# Apollo_v1.net
KiCad netlist of a schematic drawn in EAGLE
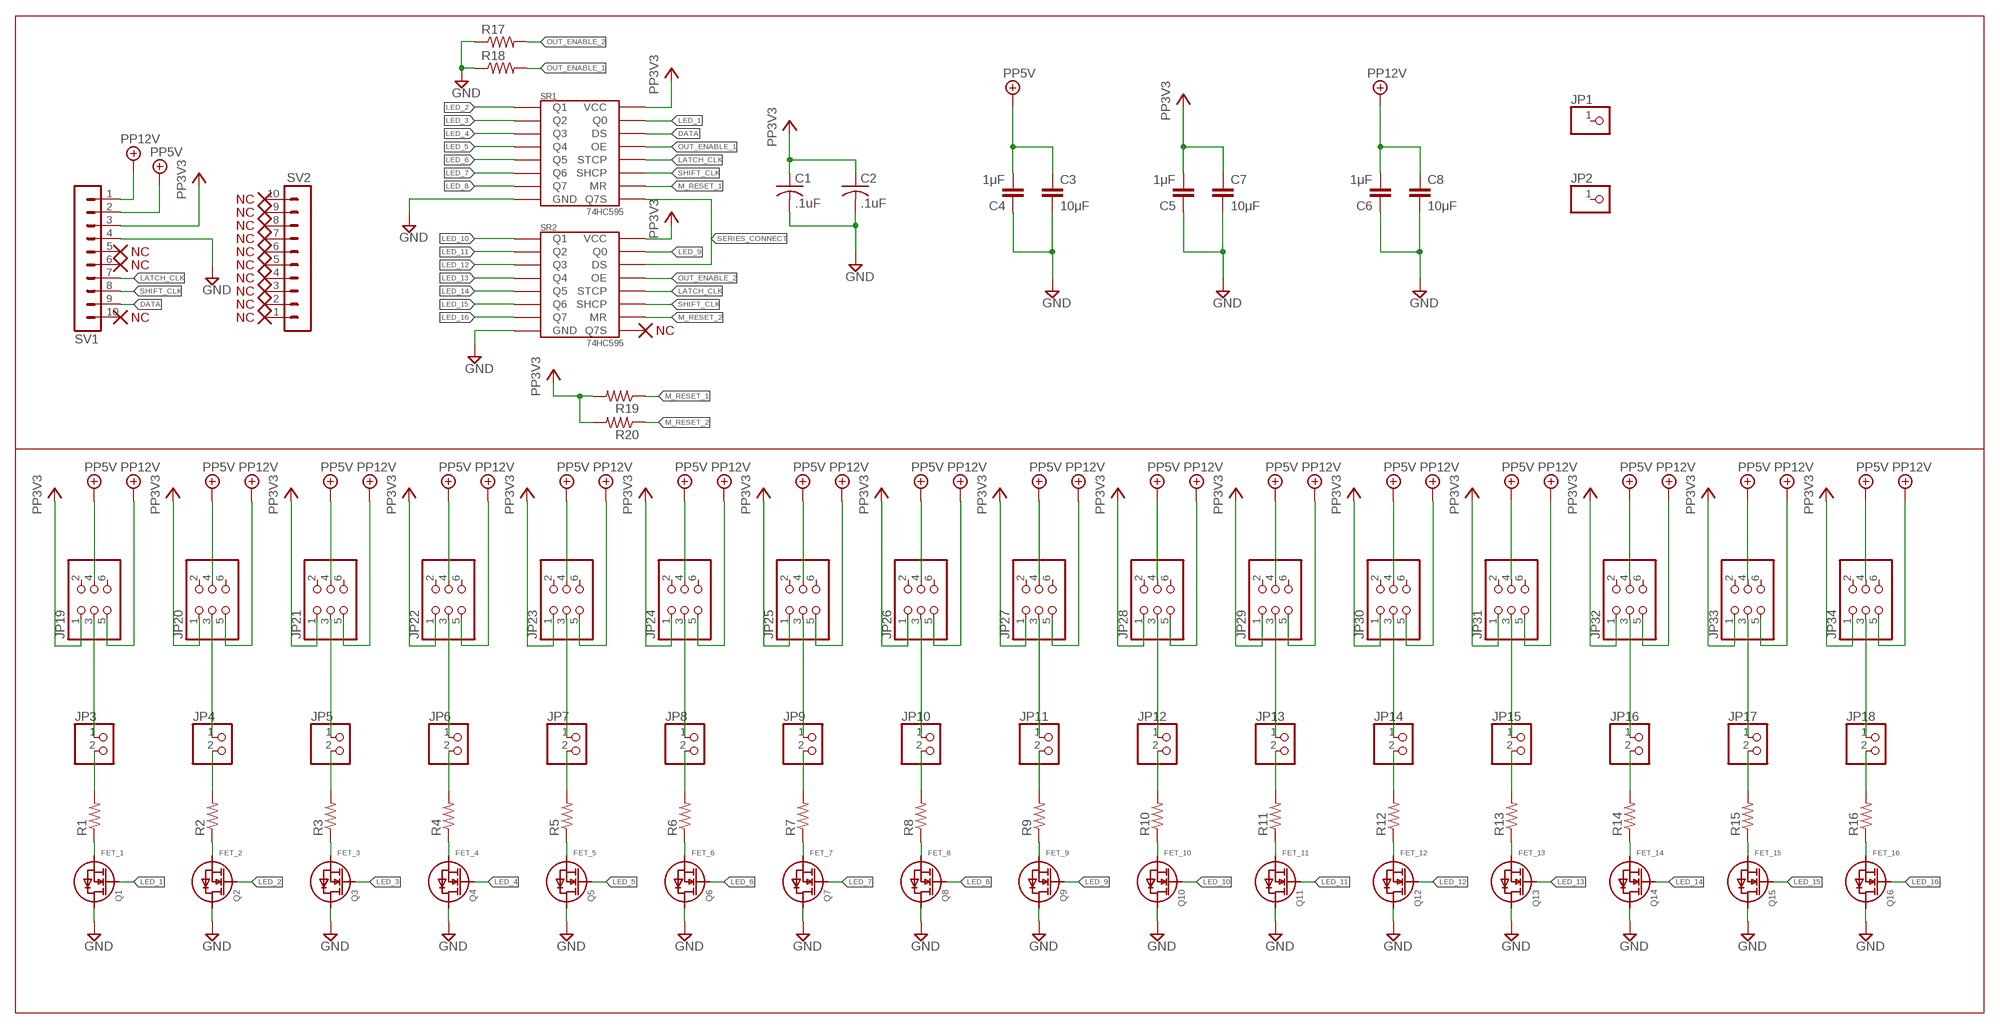
[diagram p0: schematic, sheet 1]

(export (version "E")
  (design (tool "Eeschema 10.0.6"))
  (components
    (comp (ref "C1")
      (value ".1uF")
      (footprint "eagle-import:C0603")
      (libsource (lib "eagle-import") (part "C-USC0603"))
    )
    (comp (ref "C2")
      (value ".1uF")
      (footprint "eagle-import:C0603")
      (libsource (lib "eagle-import") (part "C-USC0603"))
    )
    (comp (ref "C3")
      (value "10μF")
      (footprint "eagle-import:C1206")
      (libsource (lib "eagle-import") (part "C-EUC1206"))
    )
    (comp (ref "C4")
      (value "1μF")
      (footprint "eagle-import:C0603")
      (libsource (lib "eagle-import") (part "C-EUC0603"))
    )
    (comp (ref "C5")
      (value "1μF")
      (footprint "eagle-import:C0603")
      (libsource (lib "eagle-import") (part "C-EUC0603"))
    )
    (comp (ref "C6")
      (value "1μF")
      (footprint "eagle-import:C0603")
      (libsource (lib "eagle-import") (part "C-EUC0603"))
    )
    (comp (ref "C7")
      (value "10μF")
      (footprint "eagle-import:C1206")
      (libsource (lib "eagle-import") (part "C-EUC1206"))
    )
    (comp (ref "C8")
      (value "10μF")
      (footprint "eagle-import:C1206")
      (libsource (lib "eagle-import") (part "C-EUC1206"))
    )
    (comp (ref "JP1")
      (value "PINHD-1X1")
      (footprint "eagle-import:1X01")
      (libsource (lib "eagle-import") (part "PINHD-1X1"))
    )
    (comp (ref "JP2")
      (value "PINHD-1X1")
      (footprint "eagle-import:1X01")
      (libsource (lib "eagle-import") (part "PINHD-1X1"))
    )
    (comp (ref "JP3")
      (value "PINHD-1X2")
      (footprint "eagle-import:1X02")
      (libsource (lib "eagle-import") (part "PINHD-1X2"))
    )
    (comp (ref "JP4")
      (value "PINHD-1X2")
      (footprint "eagle-import:1X02")
      (libsource (lib "eagle-import") (part "PINHD-1X2"))
    )
    (comp (ref "JP5")
      (value "PINHD-1X2")
      (footprint "eagle-import:1X02")
      (libsource (lib "eagle-import") (part "PINHD-1X2"))
    )
    (comp (ref "JP6")
      (value "PINHD-1X2")
      (footprint "eagle-import:1X02")
      (libsource (lib "eagle-import") (part "PINHD-1X2"))
    )
    (comp (ref "JP7")
      (value "PINHD-1X2")
      (footprint "eagle-import:1X02")
      (libsource (lib "eagle-import") (part "PINHD-1X2"))
    )
    (comp (ref "JP8")
      (value "PINHD-1X2")
      (footprint "eagle-import:1X02")
      (libsource (lib "eagle-import") (part "PINHD-1X2"))
    )
    (comp (ref "JP9")
      (value "PINHD-1X2")
      (footprint "eagle-import:1X02")
      (libsource (lib "eagle-import") (part "PINHD-1X2"))
    )
    (comp (ref "JP10")
      (value "PINHD-1X2")
      (footprint "eagle-import:1X02")
      (libsource (lib "eagle-import") (part "PINHD-1X2"))
    )
    (comp (ref "JP11")
      (value "PINHD-1X2")
      (footprint "eagle-import:1X02")
      (libsource (lib "eagle-import") (part "PINHD-1X2"))
    )
    (comp (ref "JP12")
      (value "PINHD-1X2")
      (footprint "eagle-import:1X02")
      (libsource (lib "eagle-import") (part "PINHD-1X2"))
    )
    (comp (ref "JP13")
      (value "PINHD-1X2")
      (footprint "eagle-import:1X02")
      (libsource (lib "eagle-import") (part "PINHD-1X2"))
    )
    (comp (ref "JP14")
      (value "PINHD-1X2")
      (footprint "eagle-import:1X02")
      (libsource (lib "eagle-import") (part "PINHD-1X2"))
    )
    (comp (ref "JP15")
      (value "PINHD-1X2")
      (footprint "eagle-import:1X02")
      (libsource (lib "eagle-import") (part "PINHD-1X2"))
    )
    (comp (ref "JP16")
      (value "PINHD-1X2")
      (footprint "eagle-import:1X02")
      (libsource (lib "eagle-import") (part "PINHD-1X2"))
    )
    (comp (ref "JP17")
      (value "PINHD-1X2")
      (footprint "eagle-import:1X02")
      (libsource (lib "eagle-import") (part "PINHD-1X2"))
    )
    (comp (ref "JP18")
      (value "PINHD-1X2")
      (footprint "eagle-import:1X02")
      (libsource (lib "eagle-import") (part "PINHD-1X2"))
    )
    (comp (ref "JP19")
      (value "PINHD-2X3")
      (footprint "eagle-import:2X03")
      (libsource (lib "eagle-import") (part "PINHD-2X3"))
    )
    (comp (ref "JP20")
      (value "PINHD-2X3")
      (footprint "eagle-import:2X03")
      (libsource (lib "eagle-import") (part "PINHD-2X3"))
    )
    (comp (ref "JP21")
      (value "PINHD-2X3")
      (footprint "eagle-import:2X03")
      (libsource (lib "eagle-import") (part "PINHD-2X3"))
    )
    (comp (ref "JP22")
      (value "PINHD-2X3")
      (footprint "eagle-import:2X03")
      (libsource (lib "eagle-import") (part "PINHD-2X3"))
    )
    (comp (ref "JP23")
      (value "PINHD-2X3")
      (footprint "eagle-import:2X03")
      (libsource (lib "eagle-import") (part "PINHD-2X3"))
    )
    (comp (ref "JP24")
      (value "PINHD-2X3")
      (footprint "eagle-import:2X03")
      (libsource (lib "eagle-import") (part "PINHD-2X3"))
    )
    (comp (ref "JP25")
      (value "PINHD-2X3")
      (footprint "eagle-import:2X03")
      (libsource (lib "eagle-import") (part "PINHD-2X3"))
    )
    (comp (ref "JP26")
      (value "PINHD-2X3")
      (footprint "eagle-import:2X03")
      (libsource (lib "eagle-import") (part "PINHD-2X3"))
    )
    (comp (ref "JP27")
      (value "PINHD-2X3")
      (footprint "eagle-import:2X03")
      (libsource (lib "eagle-import") (part "PINHD-2X3"))
    )
    (comp (ref "JP28")
      (value "PINHD-2X3")
      (footprint "eagle-import:2X03")
      (libsource (lib "eagle-import") (part "PINHD-2X3"))
    )
    (comp (ref "JP29")
      (value "PINHD-2X3")
      (footprint "eagle-import:2X03")
      (libsource (lib "eagle-import") (part "PINHD-2X3"))
    )
    (comp (ref "JP30")
      (value "PINHD-2X3")
      (footprint "eagle-import:2X03")
      (libsource (lib "eagle-import") (part "PINHD-2X3"))
    )
    (comp (ref "JP31")
      (value "PINHD-2X3")
      (footprint "eagle-import:2X03")
      (libsource (lib "eagle-import") (part "PINHD-2X3"))
    )
    (comp (ref "JP32")
      (value "PINHD-2X3")
      (footprint "eagle-import:2X03")
      (libsource (lib "eagle-import") (part "PINHD-2X3"))
    )
    (comp (ref "JP33")
      (value "PINHD-2X3")
      (footprint "eagle-import:2X03")
      (libsource (lib "eagle-import") (part "PINHD-2X3"))
    )
    (comp (ref "JP34")
      (value "PINHD-2X3")
      (footprint "eagle-import:2X03")
      (libsource (lib "eagle-import") (part "PINHD-2X3"))
    )
    (comp (ref "Q1")
      (value "DMN6140L-7")
      (footprint "eagle-import:SOT-23-3")
      (libsource (lib "eagle-import") (part "DMN6140L-7"))
    )
    (comp (ref "Q2")
      (value "DMN6140L-7")
      (footprint "eagle-import:SOT-23-3")
      (libsource (lib "eagle-import") (part "DMN6140L-7"))
    )
    (comp (ref "Q3")
      (value "DMN6140L-7")
      (footprint "eagle-import:SOT-23-3")
      (libsource (lib "eagle-import") (part "DMN6140L-7"))
    )
    (comp (ref "Q4")
      (value "DMN6140L-7")
      (footprint "eagle-import:SOT-23-3")
      (libsource (lib "eagle-import") (part "DMN6140L-7"))
    )
    (comp (ref "Q5")
      (value "DMN6140L-7")
      (footprint "eagle-import:SOT-23-3")
      (libsource (lib "eagle-import") (part "DMN6140L-7"))
    )
    (comp (ref "Q6")
      (value "DMN6140L-7")
      (footprint "eagle-import:SOT-23-3")
      (libsource (lib "eagle-import") (part "DMN6140L-7"))
    )
    (comp (ref "Q7")
      (value "DMN6140L-7")
      (footprint "eagle-import:SOT-23-3")
      (libsource (lib "eagle-import") (part "DMN6140L-7"))
    )
    (comp (ref "Q8")
      (value "DMN6140L-7")
      (footprint "eagle-import:SOT-23-3")
      (libsource (lib "eagle-import") (part "DMN6140L-7"))
    )
    (comp (ref "Q9")
      (value "DMN6140L-7")
      (footprint "eagle-import:SOT-23-3")
      (libsource (lib "eagle-import") (part "DMN6140L-7"))
    )
    (comp (ref "Q10")
      (value "DMN6140L-7")
      (footprint "eagle-import:SOT-23-3")
      (libsource (lib "eagle-import") (part "DMN6140L-7"))
    )
    (comp (ref "Q11")
      (value "DMN6140L-7")
      (footprint "eagle-import:SOT-23-3")
      (libsource (lib "eagle-import") (part "DMN6140L-7"))
    )
    (comp (ref "Q12")
      (value "DMN6140L-7")
      (footprint "eagle-import:SOT-23-3")
      (libsource (lib "eagle-import") (part "DMN6140L-7"))
    )
    (comp (ref "Q13")
      (value "DMN6140L-7")
      (footprint "eagle-import:SOT-23-3")
      (libsource (lib "eagle-import") (part "DMN6140L-7"))
    )
    (comp (ref "Q14")
      (value "DMN6140L-7")
      (footprint "eagle-import:SOT-23-3")
      (libsource (lib "eagle-import") (part "DMN6140L-7"))
    )
    (comp (ref "Q15")
      (value "DMN6140L-7")
      (footprint "eagle-import:SOT-23-3")
      (libsource (lib "eagle-import") (part "DMN6140L-7"))
    )
    (comp (ref "Q16")
      (value "DMN6140L-7")
      (footprint "eagle-import:SOT-23-3")
      (libsource (lib "eagle-import") (part "DMN6140L-7"))
    )
    (comp (ref "R1")
      (value "R-US_R1206")
      (footprint "eagle-import:R1206")
      (libsource (lib "eagle-import") (part "R-US_R1206"))
    )
    (comp (ref "R2")
      (value "R-US_R1206")
      (footprint "eagle-import:R1206")
      (libsource (lib "eagle-import") (part "R-US_R1206"))
    )
    (comp (ref "R3")
      (value "R-US_R1206")
      (footprint "eagle-import:R1206")
      (libsource (lib "eagle-import") (part "R-US_R1206"))
    )
    (comp (ref "R4")
      (value "R-US_R1206")
      (footprint "eagle-import:R1206")
      (libsource (lib "eagle-import") (part "R-US_R1206"))
    )
    (comp (ref "R5")
      (value "R-US_R1206")
      (footprint "eagle-import:R1206")
      (libsource (lib "eagle-import") (part "R-US_R1206"))
    )
    (comp (ref "R6")
      (value "R-US_R1206")
      (footprint "eagle-import:R1206")
      (libsource (lib "eagle-import") (part "R-US_R1206"))
    )
    (comp (ref "R7")
      (value "R-US_R1206")
      (footprint "eagle-import:R1206")
      (libsource (lib "eagle-import") (part "R-US_R1206"))
    )
    (comp (ref "R8")
      (value "R-US_R1206")
      (footprint "eagle-import:R1206")
      (libsource (lib "eagle-import") (part "R-US_R1206"))
    )
    (comp (ref "R9")
      (value "R-US_R1206")
      (footprint "eagle-import:R1206")
      (libsource (lib "eagle-import") (part "R-US_R1206"))
    )
    (comp (ref "R10")
      (value "R-US_R1206")
      (footprint "eagle-import:R1206")
      (libsource (lib "eagle-import") (part "R-US_R1206"))
    )
    (comp (ref "R11")
      (value "R-US_R1206")
      (footprint "eagle-import:R1206")
      (libsource (lib "eagle-import") (part "R-US_R1206"))
    )
    (comp (ref "R12")
      (value "R-US_R1206")
      (footprint "eagle-import:R1206")
      (libsource (lib "eagle-import") (part "R-US_R1206"))
    )
    (comp (ref "R13")
      (value "R-US_R1206")
      (footprint "eagle-import:R1206")
      (libsource (lib "eagle-import") (part "R-US_R1206"))
    )
    (comp (ref "R14")
      (value "R-US_R1206")
      (footprint "eagle-import:R1206")
      (libsource (lib "eagle-import") (part "R-US_R1206"))
    )
    (comp (ref "R15")
      (value "R-US_R1206")
      (footprint "eagle-import:R1206")
      (libsource (lib "eagle-import") (part "R-US_R1206"))
    )
    (comp (ref "R16")
      (value "R-US_R1206")
      (footprint "eagle-import:R1206")
      (libsource (lib "eagle-import") (part "R-US_R1206"))
    )
    (comp (ref "R17")
      (value "R-US_R1206")
      (footprint "eagle-import:R1206")
      (libsource (lib "eagle-import") (part "R-US_R1206"))
    )
    (comp (ref "R18")
      (value "R-US_R1206")
      (footprint "eagle-import:R1206")
      (libsource (lib "eagle-import") (part "R-US_R1206"))
    )
    (comp (ref "R19")
      (value "R-US_R1206")
      (footprint "eagle-import:R1206")
      (libsource (lib "eagle-import") (part "R-US_R1206"))
    )
    (comp (ref "R20")
      (value "R-US_R1206")
      (footprint "eagle-import:R1206")
      (libsource (lib "eagle-import") (part "R-US_R1206"))
    )
    (comp (ref "SR1")
      (value "74HC595")
      (footprint "eagle-import:SO-16")
      (libsource (lib "eagle-import") (part "74HC595"))
    )
    (comp (ref "SR2")
      (value "74HC595")
      (footprint "eagle-import:SO-16")
      (libsource (lib "eagle-import") (part "74HC595"))
    )
    (comp (ref "SV1")
      (value "MA10-1")
      (footprint "eagle-import:MA10-1")
      (libsource (lib "eagle-import") (part "MA10-1"))
    )
    (comp (ref "SV2")
      (value "MA10-1")
      (footprint "eagle-import:MA10-1")
      (libsource (lib "eagle-import") (part "MA10-1"))
    )
  )
  (nets
    (net (code "1") (name "/FET_1") (class "Default")
      (node (ref "Q1") (pin "P$2") (pinfunction "S_P$2") (pintype "bidirectional"))
      (node (ref "R1") (pin "1") (pinfunction "1_1") (pintype "passive"))
    )
    (net (code "2") (name "/FET_2") (class "Default")
      (node (ref "Q2") (pin "P$2") (pinfunction "S_P$2") (pintype "bidirectional"))
      (node (ref "R2") (pin "1") (pinfunction "1_1") (pintype "passive"))
    )
    (net (code "3") (name "/FET_3") (class "Default")
      (node (ref "Q3") (pin "P$2") (pinfunction "S_P$2") (pintype "bidirectional"))
      (node (ref "R3") (pin "1") (pinfunction "1_1") (pintype "passive"))
    )
    (net (code "4") (name "/FET_4") (class "Default")
      (node (ref "Q4") (pin "P$2") (pinfunction "S_P$2") (pintype "bidirectional"))
      (node (ref "R4") (pin "1") (pinfunction "1_1") (pintype "passive"))
    )
    (net (code "5") (name "/FET_5") (class "Default")
      (node (ref "Q5") (pin "P$2") (pinfunction "S_P$2") (pintype "bidirectional"))
      (node (ref "R5") (pin "1") (pinfunction "1_1") (pintype "passive"))
    )
    (net (code "6") (name "/FET_6") (class "Default")
      (node (ref "Q6") (pin "P$2") (pinfunction "S_P$2") (pintype "bidirectional"))
      (node (ref "R6") (pin "1") (pinfunction "1_1") (pintype "passive"))
    )
    (net (code "7") (name "/FET_7") (class "Default")
      (node (ref "Q7") (pin "P$2") (pinfunction "S_P$2") (pintype "bidirectional"))
      (node (ref "R7") (pin "1") (pinfunction "1_1") (pintype "passive"))
    )
    (net (code "8") (name "/FET_8") (class "Default")
      (node (ref "Q8") (pin "P$2") (pinfunction "S_P$2") (pintype "bidirectional"))
      (node (ref "R8") (pin "1") (pinfunction "1_1") (pintype "passive"))
    )
    (net (code "9") (name "/FET_9") (class "Default")
      (node (ref "Q9") (pin "P$2") (pinfunction "S_P$2") (pintype "bidirectional"))
      (node (ref "R9") (pin "1") (pinfunction "1_1") (pintype "passive"))
    )
    (net (code "10") (name "/FET_10") (class "Default")
      (node (ref "Q10") (pin "P$2") (pinfunction "S_P$2") (pintype "bidirectional"))
      (node (ref "R10") (pin "1") (pinfunction "1_1") (pintype "passive"))
    )
    (net (code "11") (name "/FET_11") (class "Default")
      (node (ref "Q11") (pin "P$2") (pinfunction "S_P$2") (pintype "bidirectional"))
      (node (ref "R11") (pin "1") (pinfunction "1_1") (pintype "passive"))
    )
    (net (code "12") (name "/FET_12") (class "Default")
      (node (ref "Q12") (pin "P$2") (pinfunction "S_P$2") (pintype "bidirectional"))
      (node (ref "R12") (pin "1") (pinfunction "1_1") (pintype "passive"))
    )
    (net (code "13") (name "/FET_13") (class "Default")
      (node (ref "Q13") (pin "P$2") (pinfunction "S_P$2") (pintype "bidirectional"))
      (node (ref "R13") (pin "1") (pinfunction "1_1") (pintype "passive"))
    )
    (net (code "14") (name "/FET_14") (class "Default")
      (node (ref "Q14") (pin "P$2") (pinfunction "S_P$2") (pintype "bidirectional"))
      (node (ref "R14") (pin "1") (pinfunction "1_1") (pintype "passive"))
    )
    (net (code "15") (name "/FET_15") (class "Default")
      (node (ref "Q15") (pin "P$2") (pinfunction "S_P$2") (pintype "bidirectional"))
      (node (ref "R15") (pin "1") (pinfunction "1_1") (pintype "passive"))
    )
    (net (code "16") (name "/FET_16") (class "Default")
      (node (ref "Q16") (pin "P$2") (pinfunction "S_P$2") (pintype "bidirectional"))
      (node (ref "R16") (pin "1") (pinfunction "1_1") (pintype "passive"))
    )
    (net (code "17") (name "DATA") (class "Default")
      (node (ref "SR1") (pin "P$14") (pinfunction "DS_P$14") (pintype "bidirectional"))
      (node (ref "SV1") (pin "9") (pinfunction "9_9") (pintype "passive"))
    )
    (net (code "18") (name "GND") (class "Default")
      (node (ref "C1") (pin "2") (pinfunction "2_2") (pintype "passive"))
      (node (ref "C2") (pin "2") (pinfunction "2_2") (pintype "passive"))
      (node (ref "C3") (pin "2") (pinfunction "2_2") (pintype "passive"))
      (node (ref "C4") (pin "1") (pinfunction "1_1") (pintype "passive"))
      (node (ref "C5") (pin "1") (pinfunction "1_1") (pintype "passive"))
      (node (ref "C6") (pin "1") (pinfunction "1_1") (pintype "passive"))
      (node (ref "C7") (pin "2") (pinfunction "2_2") (pintype "passive"))
      (node (ref "C8") (pin "2") (pinfunction "2_2") (pintype "passive"))
      (node (ref "Q1") (pin "P$3") (pinfunction "D_P$3") (pintype "bidirectional"))
      (node (ref "Q10") (pin "P$3") (pinfunction "D_P$3") (pintype "bidirectional"))
      (node (ref "Q11") (pin "P$3") (pinfunction "D_P$3") (pintype "bidirectional"))
      (node (ref "Q12") (pin "P$3") (pinfunction "D_P$3") (pintype "bidirectional"))
      (node (ref "Q13") (pin "P$3") (pinfunction "D_P$3") (pintype "bidirectional"))
      (node (ref "Q14") (pin "P$3") (pinfunction "D_P$3") (pintype "bidirectional"))
      (node (ref "Q15") (pin "P$3") (pinfunction "D_P$3") (pintype "bidirectional"))
      (node (ref "Q16") (pin "P$3") (pinfunction "D_P$3") (pintype "bidirectional"))
      (node (ref "Q2") (pin "P$3") (pinfunction "D_P$3") (pintype "bidirectional"))
      (node (ref "Q3") (pin "P$3") (pinfunction "D_P$3") (pintype "bidirectional"))
      (node (ref "Q4") (pin "P$3") (pinfunction "D_P$3") (pintype "bidirectional"))
      (node (ref "Q5") (pin "P$3") (pinfunction "D_P$3") (pintype "bidirectional"))
      (node (ref "Q6") (pin "P$3") (pinfunction "D_P$3") (pintype "bidirectional"))
      (node (ref "Q7") (pin "P$3") (pinfunction "D_P$3") (pintype "bidirectional"))
      (node (ref "Q8") (pin "P$3") (pinfunction "D_P$3") (pintype "bidirectional"))
      (node (ref "Q9") (pin "P$3") (pinfunction "D_P$3") (pintype "bidirectional"))
      (node (ref "R17") (pin "1") (pinfunction "1_1") (pintype "passive"))
      (node (ref "R18") (pin "1") (pinfunction "1_1") (pintype "passive"))
      (node (ref "SR1") (pin "P$8") (pinfunction "GND_P$8") (pintype "bidirectional"))
      (node (ref "SR2") (pin "P$8") (pinfunction "GND_P$8") (pintype "bidirectional"))
      (node (ref "SV1") (pin "4") (pinfunction "4_4") (pintype "passive"))
    )
    (net (code "19") (name "LATCH_CLK") (class "Default")
      (node (ref "SR1") (pin "P$12") (pinfunction "STCP_P$12") (pintype "bidirectional"))
      (node (ref "SR2") (pin "P$12") (pinfunction "STCP_P$12") (pintype "bidirectional"))
      (node (ref "SV1") (pin "7") (pinfunction "7_7") (pintype "passive"))
    )
    (net (code "20") (name "LED_1") (class "Default")
      (node (ref "Q1") (pin "P$1") (pinfunction "G_P$1") (pintype "bidirectional"))
      (node (ref "SR1") (pin "P$15") (pinfunction "Q0_P$15") (pintype "bidirectional"))
    )
    (net (code "21") (name "LED_2") (class "Default")
      (node (ref "Q2") (pin "P$1") (pinfunction "G_P$1") (pintype "bidirectional"))
      (node (ref "SR1") (pin "P$1") (pinfunction "Q1_P$1") (pintype "bidirectional"))
    )
    (net (code "22") (name "LED_3") (class "Default")
      (node (ref "Q3") (pin "P$1") (pinfunction "G_P$1") (pintype "bidirectional"))
      (node (ref "SR1") (pin "P$2") (pinfunction "Q2_P$2") (pintype "bidirectional"))
    )
    (net (code "23") (name "LED_4") (class "Default")
      (node (ref "Q4") (pin "P$1") (pinfunction "G_P$1") (pintype "bidirectional"))
      (node (ref "SR1") (pin "P$3") (pinfunction "Q3_P$3") (pintype "bidirectional"))
    )
    (net (code "24") (name "LED_5") (class "Default")
      (node (ref "Q5") (pin "P$1") (pinfunction "G_P$1") (pintype "bidirectional"))
      (node (ref "SR1") (pin "P$4") (pinfunction "Q4_P$4") (pintype "bidirectional"))
    )
    (net (code "25") (name "LED_6") (class "Default")
      (node (ref "Q6") (pin "P$1") (pinfunction "G_P$1") (pintype "bidirectional"))
      (node (ref "SR1") (pin "P$5") (pinfunction "Q5_P$5") (pintype "bidirectional"))
    )
    (net (code "26") (name "LED_7") (class "Default")
      (node (ref "Q7") (pin "P$1") (pinfunction "G_P$1") (pintype "bidirectional"))
      (node (ref "SR1") (pin "P$6") (pinfunction "Q6_P$6") (pintype "bidirectional"))
    )
    (net (code "27") (name "LED_8") (class "Default")
      (node (ref "Q8") (pin "P$1") (pinfunction "G_P$1") (pintype "bidirectional"))
      (node (ref "SR1") (pin "P$7") (pinfunction "Q7_P$7") (pintype "bidirectional"))
    )
    (net (code "28") (name "LED_9") (class "Default")
      (node (ref "Q9") (pin "P$1") (pinfunction "G_P$1") (pintype "bidirectional"))
      (node (ref "SR2") (pin "P$15") (pinfunction "Q0_P$15") (pintype "bidirectional"))
    )
    (net (code "29") (name "LED_10") (class "Default")
      (node (ref "Q10") (pin "P$1") (pinfunction "G_P$1") (pintype "bidirectional"))
      (node (ref "SR2") (pin "P$1") (pinfunction "Q1_P$1") (pintype "bidirectional"))
    )
    (net (code "30") (name "LED_11") (class "Default")
      (node (ref "Q11") (pin "P$1") (pinfunction "G_P$1") (pintype "bidirectional"))
      (node (ref "SR2") (pin "P$2") (pinfunction "Q2_P$2") (pintype "bidirectional"))
    )
    (net (code "31") (name "LED_12") (class "Default")
      (node (ref "Q12") (pin "P$1") (pinfunction "G_P$1") (pintype "bidirectional"))
      (node (ref "SR2") (pin "P$3") (pinfunction "Q3_P$3") (pintype "bidirectional"))
    )
    (net (code "32") (name "LED_13") (class "Default")
      (node (ref "Q13") (pin "P$1") (pinfunction "G_P$1") (pintype "bidirectional"))
      (node (ref "SR2") (pin "P$4") (pinfunction "Q4_P$4") (pintype "bidirectional"))
    )
    (net (code "33") (name "LED_14") (class "Default")
      (node (ref "Q14") (pin "P$1") (pinfunction "G_P$1") (pintype "bidirectional"))
      (node (ref "SR2") (pin "P$5") (pinfunction "Q5_P$5") (pintype "bidirectional"))
    )
    (net (code "34") (name "LED_15") (class "Default")
      (node (ref "Q15") (pin "P$1") (pinfunction "G_P$1") (pintype "bidirectional"))
      (node (ref "SR2") (pin "P$6") (pinfunction "Q6_P$6") (pintype "bidirectional"))
    )
    (net (code "35") (name "LED_16") (class "Default")
      (node (ref "Q16") (pin "P$1") (pinfunction "G_P$1") (pintype "bidirectional"))
      (node (ref "SR2") (pin "P$7") (pinfunction "Q7_P$7") (pintype "bidirectional"))
    )
    (net (code "36") (name "M_RESET_1") (class "Default")
      (node (ref "R19") (pin "1") (pinfunction "1_1") (pintype "passive"))
      (node (ref "SR1") (pin "P$10") (pinfunction "MR_P$10") (pintype "bidirectional"))
    )
    (net (code "37") (name "M_RESET_2") (class "Default")
      (node (ref "R20") (pin "1") (pinfunction "1_1") (pintype "passive"))
      (node (ref "SR2") (pin "P$10") (pinfunction "MR_P$10") (pintype "bidirectional"))
    )
    (net (code "38") (name "Net-(JP3-Pad2)") (class "Default")
      (node (ref "JP3") (pin "2") (pinfunction "2_2") (pintype "passive"))
      (node (ref "R1") (pin "2") (pinfunction "2_2") (pintype "passive"))
    )
    (net (code "39") (name "Net-(JP4-Pad2)") (class "Default")
      (node (ref "JP4") (pin "2") (pinfunction "2_2") (pintype "passive"))
      (node (ref "R2") (pin "2") (pinfunction "2_2") (pintype "passive"))
    )
    (net (code "40") (name "Net-(JP5-Pad2)") (class "Default")
      (node (ref "JP5") (pin "2") (pinfunction "2_2") (pintype "passive"))
      (node (ref "R3") (pin "2") (pinfunction "2_2") (pintype "passive"))
    )
    (net (code "41") (name "Net-(JP6-Pad2)") (class "Default")
      (node (ref "JP6") (pin "2") (pinfunction "2_2") (pintype "passive"))
      (node (ref "R4") (pin "2") (pinfunction "2_2") (pintype "passive"))
    )
    (net (code "42") (name "Net-(JP7-Pad2)") (class "Default")
      (node (ref "JP7") (pin "2") (pinfunction "2_2") (pintype "passive"))
      (node (ref "R5") (pin "2") (pinfunction "2_2") (pintype "passive"))
    )
    (net (code "43") (name "Net-(JP8-Pad2)") (class "Default")
      (node (ref "JP8") (pin "2") (pinfunction "2_2") (pintype "passive"))
      (node (ref "R6") (pin "2") (pinfunction "2_2") (pintype "passive"))
    )
    (net (code "44") (name "Net-(JP9-Pad2)") (class "Default")
      (node (ref "JP9") (pin "2") (pinfunction "2_2") (pintype "passive"))
      (node (ref "R7") (pin "2") (pinfunction "2_2") (pintype "passive"))
    )
    (net (code "45") (name "Net-(JP10-Pad1)") (class "Default")
      (node (ref "JP10") (pin "1") (pinfunction "1_1") (pintype "passive"))
      (node (ref "JP26") (pin "3") (pinfunction "3_3") (pintype "passive"))
    )
    (net (code "46") (name "Net-(JP10-Pad2)") (class "Default")
      (node (ref "JP10") (pin "2") (pinfunction "2_2") (pintype "passive"))
      (node (ref "R8") (pin "2") (pinfunction "2_2") (pintype "passive"))
    )
    (net (code "47") (name "Net-(JP11-Pad1)") (class "Default")
      (node (ref "JP11") (pin "1") (pinfunction "1_1") (pintype "passive"))
      (node (ref "JP27") (pin "3") (pinfunction "3_3") (pintype "passive"))
    )
    (net (code "48") (name "Net-(JP11-Pad2)") (class "Default")
      (node (ref "JP11") (pin "2") (pinfunction "2_2") (pintype "passive"))
      (node (ref "R9") (pin "2") (pinfunction "2_2") (pintype "passive"))
    )
    (net (code "49") (name "Net-(JP12-Pad1)") (class "Default")
      (node (ref "JP12") (pin "1") (pinfunction "1_1") (pintype "passive"))
      (node (ref "JP28") (pin "3") (pinfunction "3_3") (pintype "passive"))
    )
    (net (code "50") (name "Net-(JP12-Pad2)") (class "Default")
      (node (ref "JP12") (pin "2") (pinfunction "2_2") (pintype "passive"))
      (node (ref "R10") (pin "2") (pinfunction "2_2") (pintype "passive"))
    )
    (net (code "51") (name "Net-(JP13-Pad1)") (class "Default")
      (node (ref "JP13") (pin "1") (pinfunction "1_1") (pintype "passive"))
      (node (ref "JP29") (pin "3") (pinfunction "3_3") (pintype "passive"))
    )
    (net (code "52") (name "Net-(JP13-Pad2)") (class "Default")
      (node (ref "JP13") (pin "2") (pinfunction "2_2") (pintype "passive"))
      (node (ref "R11") (pin "2") (pinfunction "2_2") (pintype "passive"))
    )
    (net (code "53") (name "Net-(JP14-Pad1)") (class "Default")
      (node (ref "JP14") (pin "1") (pinfunction "1_1") (pintype "passive"))
      (node (ref "JP30") (pin "3") (pinfunction "3_3") (pintype "passive"))
    )
    (net (code "54") (name "Net-(JP14-Pad2)") (class "Default")
      (node (ref "JP14") (pin "2") (pinfunction "2_2") (pintype "passive"))
      (node (ref "R12") (pin "2") (pinfunction "2_2") (pintype "passive"))
    )
    (net (code "55") (name "Net-(JP15-Pad1)") (class "Default")
      (node (ref "JP15") (pin "1") (pinfunction "1_1") (pintype "passive"))
      (node (ref "JP31") (pin "3") (pinfunction "3_3") (pintype "passive"))
    )
    (net (code "56") (name "Net-(JP15-Pad2)") (class "Default")
      (node (ref "JP15") (pin "2") (pinfunction "2_2") (pintype "passive"))
      (node (ref "R13") (pin "2") (pinfunction "2_2") (pintype "passive"))
    )
    (net (code "57") (name "Net-(JP16-Pad1)") (class "Default")
      (node (ref "JP16") (pin "1") (pinfunction "1_1") (pintype "passive"))
      (node (ref "JP32") (pin "3") (pinfunction "3_3") (pintype "passive"))
    )
    (net (code "58") (name "Net-(JP16-Pad2)") (class "Default")
      (node (ref "JP16") (pin "2") (pinfunction "2_2") (pintype "passive"))
      (node (ref "R14") (pin "2") (pinfunction "2_2") (pintype "passive"))
    )
    (net (code "59") (name "Net-(JP17-Pad1)") (class "Default")
      (node (ref "JP17") (pin "1") (pinfunction "1_1") (pintype "passive"))
      (node (ref "JP33") (pin "3") (pinfunction "3_3") (pintype "passive"))
    )
    (net (code "60") (name "Net-(JP17-Pad2)") (class "Default")
      (node (ref "JP17") (pin "2") (pinfunction "2_2") (pintype "passive"))
      (node (ref "R15") (pin "2") (pinfunction "2_2") (pintype "passive"))
    )
    (net (code "61") (name "Net-(JP18-Pad1)") (class "Default")
      (node (ref "JP18") (pin "1") (pinfunction "1_1") (pintype "passive"))
      (node (ref "JP34") (pin "3") (pinfunction "3_3") (pintype "passive"))
    )
    (net (code "62") (name "Net-(JP18-Pad2)") (class "Default")
      (node (ref "JP18") (pin "2") (pinfunction "2_2") (pintype "passive"))
      (node (ref "R16") (pin "2") (pinfunction "2_2") (pintype "passive"))
    )
    (net (code "63") (name "Net-(JP19-Pad3)") (class "Default")
      (node (ref "JP19") (pin "3") (pinfunction "3_3") (pintype "passive"))
      (node (ref "JP3") (pin "1") (pinfunction "1_1") (pintype "passive"))
    )
    (net (code "64") (name "Net-(JP20-Pad3)") (class "Default")
      (node (ref "JP20") (pin "3") (pinfunction "3_3") (pintype "passive"))
      (node (ref "JP4") (pin "1") (pinfunction "1_1") (pintype "passive"))
    )
    (net (code "65") (name "Net-(JP21-Pad3)") (class "Default")
      (node (ref "JP21") (pin "3") (pinfunction "3_3") (pintype "passive"))
      (node (ref "JP5") (pin "1") (pinfunction "1_1") (pintype "passive"))
    )
    (net (code "66") (name "Net-(JP22-Pad3)") (class "Default")
      (node (ref "JP22") (pin "3") (pinfunction "3_3") (pintype "passive"))
      (node (ref "JP6") (pin "1") (pinfunction "1_1") (pintype "passive"))
    )
    (net (code "67") (name "Net-(JP23-Pad3)") (class "Default")
      (node (ref "JP23") (pin "3") (pinfunction "3_3") (pintype "passive"))
      (node (ref "JP7") (pin "1") (pinfunction "1_1") (pintype "passive"))
    )
    (net (code "68") (name "Net-(JP24-Pad3)") (class "Default")
      (node (ref "JP24") (pin "3") (pinfunction "3_3") (pintype "passive"))
      (node (ref "JP8") (pin "1") (pinfunction "1_1") (pintype "passive"))
    )
    (net (code "69") (name "Net-(JP25-Pad3)") (class "Default")
      (node (ref "JP25") (pin "3") (pinfunction "3_3") (pintype "passive"))
      (node (ref "JP9") (pin "1") (pinfunction "1_1") (pintype "passive"))
    )
    (net (code "70") (name "OUT_ENABLE_1") (class "Default")
      (node (ref "R18") (pin "2") (pinfunction "2_2") (pintype "passive"))
      (node (ref "SR1") (pin "P$13") (pinfunction "OE_P$13") (pintype "bidirectional"))
    )
    (net (code "71") (name "OUT_ENABLE_2") (class "Default")
      (node (ref "R17") (pin "2") (pinfunction "2_2") (pintype "passive"))
      (node (ref "SR2") (pin "P$13") (pinfunction "OE_P$13") (pintype "bidirectional"))
    )
    (net (code "72") (name "PP3V3") (class "Default")
      (node (ref "C1") (pin "1") (pinfunction "1_1") (pintype "passive"))
      (node (ref "C2") (pin "1") (pinfunction "1_1") (pintype "passive"))
      (node (ref "C5") (pin "2") (pinfunction "2_2") (pintype "passive"))
      (node (ref "C7") (pin "1") (pinfunction "1_1") (pintype "passive"))
      (node (ref "JP19") (pin "1") (pinfunction "1_1") (pintype "passive"))
      (node (ref "JP20") (pin "1") (pinfunction "1_1") (pintype "passive"))
      (node (ref "JP21") (pin "1") (pinfunction "1_1") (pintype "passive"))
      (node (ref "JP22") (pin "1") (pinfunction "1_1") (pintype "passive"))
      (node (ref "JP23") (pin "1") (pinfunction "1_1") (pintype "passive"))
      (node (ref "JP24") (pin "1") (pinfunction "1_1") (pintype "passive"))
      (node (ref "JP25") (pin "1") (pinfunction "1_1") (pintype "passive"))
      (node (ref "JP26") (pin "1") (pinfunction "1_1") (pintype "passive"))
      (node (ref "JP27") (pin "1") (pinfunction "1_1") (pintype "passive"))
      (node (ref "JP28") (pin "1") (pinfunction "1_1") (pintype "passive"))
      (node (ref "JP29") (pin "1") (pinfunction "1_1") (pintype "passive"))
      (node (ref "JP30") (pin "1") (pinfunction "1_1") (pintype "passive"))
      (node (ref "JP31") (pin "1") (pinfunction "1_1") (pintype "passive"))
      (node (ref "JP32") (pin "1") (pinfunction "1_1") (pintype "passive"))
      (node (ref "JP33") (pin "1") (pinfunction "1_1") (pintype "passive"))
      (node (ref "JP34") (pin "1") (pinfunction "1_1") (pintype "passive"))
      (node (ref "R19") (pin "2") (pinfunction "2_2") (pintype "passive"))
      (node (ref "R20") (pin "2") (pinfunction "2_2") (pintype "passive"))
      (node (ref "SR1") (pin "P$16") (pinfunction "VCC_P$16") (pintype "bidirectional"))
      (node (ref "SR2") (pin "P$16") (pinfunction "VCC_P$16") (pintype "bidirectional"))
      (node (ref "SV1") (pin "3") (pinfunction "3_3") (pintype "passive"))
    )
    (net (code "73") (name "PP5V") (class "Default")
      (node (ref "C3") (pin "1") (pinfunction "1_1") (pintype "passive"))
      (node (ref "C4") (pin "2") (pinfunction "2_2") (pintype "passive"))
      (node (ref "JP19") (pin "4") (pinfunction "4_4") (pintype "passive"))
      (node (ref "JP20") (pin "4") (pinfunction "4_4") (pintype "passive"))
      (node (ref "JP21") (pin "4") (pinfunction "4_4") (pintype "passive"))
      (node (ref "JP22") (pin "4") (pinfunction "4_4") (pintype "passive"))
      (node (ref "JP23") (pin "4") (pinfunction "4_4") (pintype "passive"))
      (node (ref "JP24") (pin "4") (pinfunction "4_4") (pintype "passive"))
      (node (ref "JP25") (pin "4") (pinfunction "4_4") (pintype "passive"))
      (node (ref "JP26") (pin "4") (pinfunction "4_4") (pintype "passive"))
      (node (ref "JP27") (pin "4") (pinfunction "4_4") (pintype "passive"))
      (node (ref "JP28") (pin "4") (pinfunction "4_4") (pintype "passive"))
      (node (ref "JP29") (pin "4") (pinfunction "4_4") (pintype "passive"))
      (node (ref "JP30") (pin "4") (pinfunction "4_4") (pintype "passive"))
      (node (ref "JP31") (pin "4") (pinfunction "4_4") (pintype "passive"))
      (node (ref "JP32") (pin "4") (pinfunction "4_4") (pintype "passive"))
      (node (ref "JP33") (pin "4") (pinfunction "4_4") (pintype "passive"))
      (node (ref "JP34") (pin "4") (pinfunction "4_4") (pintype "passive"))
      (node (ref "SV1") (pin "2") (pinfunction "2_2") (pintype "passive"))
    )
    (net (code "74") (name "PP12V") (class "Default")
      (node (ref "C6") (pin "2") (pinfunction "2_2") (pintype "passive"))
      (node (ref "C8") (pin "1") (pinfunction "1_1") (pintype "passive"))
      (node (ref "JP19") (pin "5") (pinfunction "5_5") (pintype "passive"))
      (node (ref "JP20") (pin "5") (pinfunction "5_5") (pintype "passive"))
      (node (ref "JP21") (pin "5") (pinfunction "5_5") (pintype "passive"))
      (node (ref "JP22") (pin "5") (pinfunction "5_5") (pintype "passive"))
      (node (ref "JP23") (pin "5") (pinfunction "5_5") (pintype "passive"))
      (node (ref "JP24") (pin "5") (pinfunction "5_5") (pintype "passive"))
      (node (ref "JP25") (pin "5") (pinfunction "5_5") (pintype "passive"))
      (node (ref "JP26") (pin "5") (pinfunction "5_5") (pintype "passive"))
      (node (ref "JP27") (pin "5") (pinfunction "5_5") (pintype "passive"))
      (node (ref "JP28") (pin "5") (pinfunction "5_5") (pintype "passive"))
      (node (ref "JP29") (pin "5") (pinfunction "5_5") (pintype "passive"))
      (node (ref "JP30") (pin "5") (pinfunction "5_5") (pintype "passive"))
      (node (ref "JP31") (pin "5") (pinfunction "5_5") (pintype "passive"))
      (node (ref "JP32") (pin "5") (pinfunction "5_5") (pintype "passive"))
      (node (ref "JP33") (pin "5") (pinfunction "5_5") (pintype "passive"))
      (node (ref "JP34") (pin "5") (pinfunction "5_5") (pintype "passive"))
      (node (ref "SV1") (pin "1") (pinfunction "1_1") (pintype "passive"))
    )
    (net (code "75") (name "SERIES_CONNECT") (class "Default")
      (node (ref "SR1") (pin "P$9") (pinfunction "Q7S_P$9") (pintype "bidirectional"))
      (node (ref "SR2") (pin "P$14") (pinfunction "DS_P$14") (pintype "bidirectional"))
    )
    (net (code "76") (name "SHIFT_CLK") (class "Default")
      (node (ref "SR1") (pin "P$11") (pinfunction "SHCP_P$11") (pintype "bidirectional"))
      (node (ref "SR2") (pin "P$11") (pinfunction "SHCP_P$11") (pintype "bidirectional"))
      (node (ref "SV1") (pin "8") (pinfunction "8_8") (pintype "passive"))
    )
    (net (code "77") (name "unconnected-(JP1-Pad1)") (class "Default")
      (node (ref "JP1") (pin "1") (pinfunction "1_1") (pintype "passive"))
    )
    (net (code "78") (name "unconnected-(JP2-Pad1)") (class "Default")
      (node (ref "JP2") (pin "1") (pinfunction "1_1") (pintype "passive"))
    )
    (net (code "79") (name "unconnected-(JP19-Pad2)") (class "Default")
      (node (ref "JP19") (pin "2") (pinfunction "2_2") (pintype "passive"))
    )
    (net (code "80") (name "unconnected-(JP19-Pad6)") (class "Default")
      (node (ref "JP19") (pin "6") (pinfunction "6_6") (pintype "passive"))
    )
    (net (code "81") (name "unconnected-(JP20-Pad2)") (class "Default")
      (node (ref "JP20") (pin "2") (pinfunction "2_2") (pintype "passive"))
    )
    (net (code "82") (name "unconnected-(JP20-Pad6)") (class "Default")
      (node (ref "JP20") (pin "6") (pinfunction "6_6") (pintype "passive"))
    )
    (net (code "83") (name "unconnected-(JP21-Pad2)") (class "Default")
      (node (ref "JP21") (pin "2") (pinfunction "2_2") (pintype "passive"))
    )
    (net (code "84") (name "unconnected-(JP21-Pad6)") (class "Default")
      (node (ref "JP21") (pin "6") (pinfunction "6_6") (pintype "passive"))
    )
    (net (code "85") (name "unconnected-(JP22-Pad2)") (class "Default")
      (node (ref "JP22") (pin "2") (pinfunction "2_2") (pintype "passive"))
    )
    (net (code "86") (name "unconnected-(JP22-Pad6)") (class "Default")
      (node (ref "JP22") (pin "6") (pinfunction "6_6") (pintype "passive"))
    )
    (net (code "87") (name "unconnected-(JP23-Pad2)") (class "Default")
      (node (ref "JP23") (pin "2") (pinfunction "2_2") (pintype "passive"))
    )
    (net (code "88") (name "unconnected-(JP23-Pad6)") (class "Default")
      (node (ref "JP23") (pin "6") (pinfunction "6_6") (pintype "passive"))
    )
    (net (code "89") (name "unconnected-(JP24-Pad2)") (class "Default")
      (node (ref "JP24") (pin "2") (pinfunction "2_2") (pintype "passive"))
    )
    (net (code "90") (name "unconnected-(JP24-Pad6)") (class "Default")
      (node (ref "JP24") (pin "6") (pinfunction "6_6") (pintype "passive"))
    )
    (net (code "91") (name "unconnected-(JP25-Pad2)") (class "Default")
      (node (ref "JP25") (pin "2") (pinfunction "2_2") (pintype "passive"))
    )
    (net (code "92") (name "unconnected-(JP25-Pad6)") (class "Default")
      (node (ref "JP25") (pin "6") (pinfunction "6_6") (pintype "passive"))
    )
    (net (code "93") (name "unconnected-(JP26-Pad2)") (class "Default")
      (node (ref "JP26") (pin "2") (pinfunction "2_2") (pintype "passive"))
    )
    (net (code "94") (name "unconnected-(JP26-Pad6)") (class "Default")
      (node (ref "JP26") (pin "6") (pinfunction "6_6") (pintype "passive"))
    )
    (net (code "95") (name "unconnected-(JP27-Pad2)") (class "Default")
      (node (ref "JP27") (pin "2") (pinfunction "2_2") (pintype "passive"))
    )
    (net (code "96") (name "unconnected-(JP27-Pad6)") (class "Default")
      (node (ref "JP27") (pin "6") (pinfunction "6_6") (pintype "passive"))
    )
    (net (code "97") (name "unconnected-(JP28-Pad2)") (class "Default")
      (node (ref "JP28") (pin "2") (pinfunction "2_2") (pintype "passive"))
    )
    (net (code "98") (name "unconnected-(JP28-Pad6)") (class "Default")
      (node (ref "JP28") (pin "6") (pinfunction "6_6") (pintype "passive"))
    )
    (net (code "99") (name "unconnected-(JP29-Pad2)") (class "Default")
      (node (ref "JP29") (pin "2") (pinfunction "2_2") (pintype "passive"))
    )
    (net (code "100") (name "unconnected-(JP29-Pad6)") (class "Default")
      (node (ref "JP29") (pin "6") (pinfunction "6_6") (pintype "passive"))
    )
    (net (code "101") (name "unconnected-(JP30-Pad2)") (class "Default")
      (node (ref "JP30") (pin "2") (pinfunction "2_2") (pintype "passive"))
    )
    (net (code "102") (name "unconnected-(JP30-Pad6)") (class "Default")
      (node (ref "JP30") (pin "6") (pinfunction "6_6") (pintype "passive"))
    )
    (net (code "103") (name "unconnected-(JP31-Pad2)") (class "Default")
      (node (ref "JP31") (pin "2") (pinfunction "2_2") (pintype "passive"))
    )
    (net (code "104") (name "unconnected-(JP31-Pad6)") (class "Default")
      (node (ref "JP31") (pin "6") (pinfunction "6_6") (pintype "passive"))
    )
    (net (code "105") (name "unconnected-(JP32-Pad2)") (class "Default")
      (node (ref "JP32") (pin "2") (pinfunction "2_2") (pintype "passive"))
    )
    (net (code "106") (name "unconnected-(JP32-Pad6)") (class "Default")
      (node (ref "JP32") (pin "6") (pinfunction "6_6") (pintype "passive"))
    )
    (net (code "107") (name "unconnected-(JP33-Pad2)") (class "Default")
      (node (ref "JP33") (pin "2") (pinfunction "2_2") (pintype "passive"))
    )
    (net (code "108") (name "unconnected-(JP33-Pad6)") (class "Default")
      (node (ref "JP33") (pin "6") (pinfunction "6_6") (pintype "passive"))
    )
    (net (code "109") (name "unconnected-(JP34-Pad2)") (class "Default")
      (node (ref "JP34") (pin "2") (pinfunction "2_2") (pintype "passive"))
    )
    (net (code "110") (name "unconnected-(JP34-Pad6)") (class "Default")
      (node (ref "JP34") (pin "6") (pinfunction "6_6") (pintype "passive"))
    )
    (net (code "111") (name "unconnected-(SR2-Q7S-PadP$9)") (class "Default")
      (node (ref "SR2") (pin "P$9") (pinfunction "Q7S_P$9") (pintype "bidirectional"))
    )
    (net (code "112") (name "unconnected-(SV1-Pad5)") (class "Default")
      (node (ref "SV1") (pin "5") (pinfunction "5_5") (pintype "passive"))
    )
    (net (code "113") (name "unconnected-(SV1-Pad6)") (class "Default")
      (node (ref "SV1") (pin "6") (pinfunction "6_6") (pintype "passive"))
    )
    (net (code "114") (name "unconnected-(SV1-Pad10)") (class "Default")
      (node (ref "SV1") (pin "10") (pinfunction "10_10") (pintype "passive"))
    )
    (net (code "115") (name "unconnected-(SV2-Pad1)") (class "Default")
      (node (ref "SV2") (pin "1") (pinfunction "1_1") (pintype "passive"))
    )
    (net (code "116") (name "unconnected-(SV2-Pad2)") (class "Default")
      (node (ref "SV2") (pin "2") (pinfunction "2_2") (pintype "passive"))
    )
    (net (code "117") (name "unconnected-(SV2-Pad3)") (class "Default")
      (node (ref "SV2") (pin "3") (pinfunction "3_3") (pintype "passive"))
    )
    (net (code "118") (name "unconnected-(SV2-Pad4)") (class "Default")
      (node (ref "SV2") (pin "4") (pinfunction "4_4") (pintype "passive"))
    )
    (net (code "119") (name "unconnected-(SV2-Pad5)") (class "Default")
      (node (ref "SV2") (pin "5") (pinfunction "5_5") (pintype "passive"))
    )
    (net (code "120") (name "unconnected-(SV2-Pad6)") (class "Default")
      (node (ref "SV2") (pin "6") (pinfunction "6_6") (pintype "passive"))
    )
    (net (code "121") (name "unconnected-(SV2-Pad7)") (class "Default")
      (node (ref "SV2") (pin "7") (pinfunction "7_7") (pintype "passive"))
    )
    (net (code "122") (name "unconnected-(SV2-Pad8)") (class "Default")
      (node (ref "SV2") (pin "8") (pinfunction "8_8") (pintype "passive"))
    )
    (net (code "123") (name "unconnected-(SV2-Pad9)") (class "Default")
      (node (ref "SV2") (pin "9") (pinfunction "9_9") (pintype "passive"))
    )
    (net (code "124") (name "unconnected-(SV2-Pad10)") (class "Default")
      (node (ref "SV2") (pin "10") (pinfunction "10_10") (pintype "passive"))
    )
  )
)
